# ECUCheater.net
KiCad netlist of a schematic drawn in Altium Designer
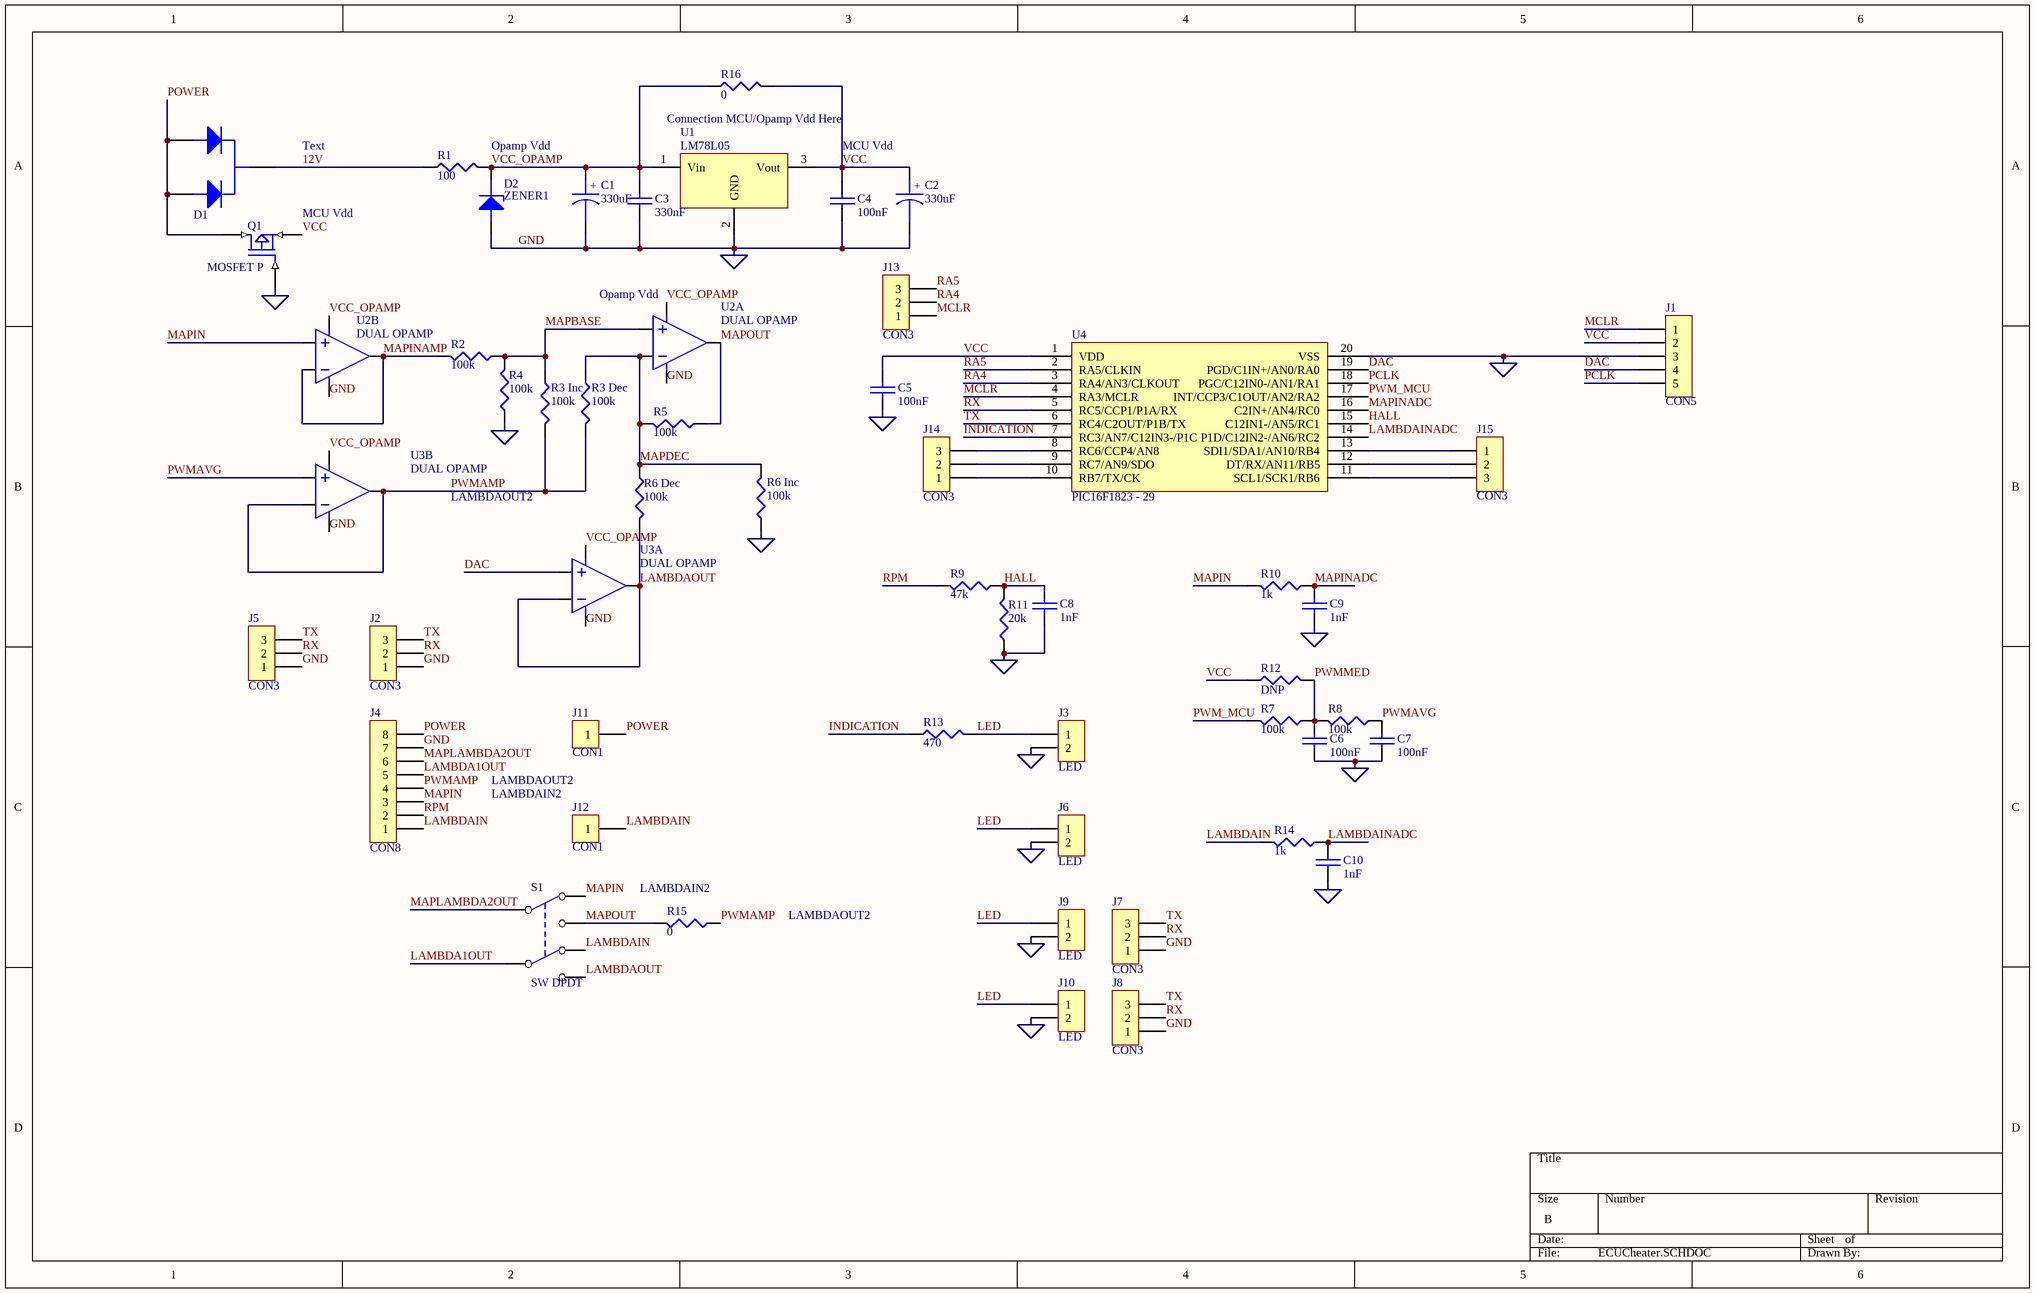
[diagram p0: ECUCheater.SCHDOC]

(export (version "E")
  (design (tool "Eeschema 10.0.6"))
  (components
    (comp (ref "C1")
      (value "330uF")
      (footprint "3528 + RA 6.3mm NOT ROUND")
      (description "Capacitor")
      (libsource (lib "*") (part "CAPACITOR POL"))
    )
    (comp (ref "C2")
      (value "330uF")
      (footprint "3528 + RA 6.3mm NOT ROUND")
      (description "Capacitor")
      (libsource (lib "*") (part "CAPACITOR POL"))
    )
    (comp (ref "C3")
      (value "330nF")
      (footprint "0805")
      (description "Capacitor")
      (libsource (lib "*") (part "CAP"))
    )
    (comp (ref "C4")
      (value "100nF")
      (footprint "0805")
      (description "Capacitor")
      (libsource (lib "*") (part "CAP"))
    )
    (comp (ref "C5")
      (value "100nF")
      (footprint "0603 CAP")
      (description "Capacitor")
      (libsource (lib "*") (part "CAP"))
    )
    (comp (ref "C6")
      (value "100nF")
      (footprint "0603 CAP")
      (description "Capacitor")
      (libsource (lib "*") (part "CAP"))
    )
    (comp (ref "C7")
      (value "100nF")
      (footprint "0603 CAP")
      (description "Capacitor")
      (libsource (lib "*") (part "CAP"))
    )
    (comp (ref "C8")
      (value "1nF")
      (footprint "0603 CAP")
      (description "Capacitor")
      (libsource (lib "*") (part "CAP"))
    )
    (comp (ref "C9")
      (value "1nF")
      (footprint "0603 CAP")
      (description "Capacitor")
      (libsource (lib "*") (part "CAP"))
    )
    (comp (ref "C10")
      (value "1nF")
      (footprint "0603 CAP")
      (description "Capacitor")
      (libsource (lib "*") (part "CAP"))
    )
    (comp (ref "D1")
      (value "DUAL DIODE BAV70")
      (footprint "SOT-23")
      (libsource (lib "Devices") (part "DUAL DIODE BAV70"))
    )
    (comp (ref "D2")
      (value "ZENER1")
      (footprint "SOT-23")
      (description "Zener Diode")
      (libsource (lib "Miscellaneous Devices") (part "ZENER1"))
    )
    (comp (ref "J1")
      (value "CON5")
      (footprint "SIP5 - PGM")
      (description "Connector")
      (libsource (lib "Miscellaneous Devices") (part "CON5"))
    )
    (comp (ref "J2")
      (value "CON3")
      (footprint "SIP3")
      (description "Connector")
      (libsource (lib "Miscellaneous Devices") (part "CON3"))
    )
    (comp (ref "J3")
      (value "LED")
      (footprint "SIP2")
      (description "Connector")
      (libsource (lib "Miscellaneous Devices") (part "CON2"))
    )
    (comp (ref "J4")
      (value "CON8")
      (footprint "HD-351 8P")
      (description "Connector")
      (libsource (lib "Miscellaneous Devices") (part "CON8"))
    )
    (comp (ref "J5")
      (value "CON3")
      (footprint "SIP3")
      (description "Connector")
      (libsource (lib "Miscellaneous Devices") (part "CON3"))
    )
    (comp (ref "J6")
      (value "LED")
      (footprint "SIP2")
      (description "Connector")
      (libsource (lib "Miscellaneous Devices") (part "CON2"))
    )
    (comp (ref "J7")
      (value "CON3")
      (footprint "SIP3")
      (description "Connector")
      (libsource (lib "Miscellaneous Devices") (part "CON3"))
    )
    (comp (ref "J8")
      (value "CON3")
      (footprint "SIP3")
      (description "Connector")
      (libsource (lib "Miscellaneous Devices") (part "CON3"))
    )
    (comp (ref "J9")
      (value "LED")
      (footprint "SIP2")
      (description "Connector")
      (libsource (lib "Miscellaneous Devices") (part "CON2"))
    )
    (comp (ref "J10")
      (value "LED")
      (footprint "SIP2")
      (description "Connector")
      (libsource (lib "Miscellaneous Devices") (part "CON2"))
    )
    (comp (ref "J11")
      (value "CON1")
      (footprint "HD-351 1P")
      (description "Connector")
      (libsource (lib "Miscellaneous Devices") (part "CON1"))
    )
    (comp (ref "J12")
      (value "CON1")
      (footprint "HD-351 1P")
      (description "Connector")
      (libsource (lib "Miscellaneous Devices") (part "CON1"))
    )
    (comp (ref "J13")
      (value "CON3")
      (footprint "SIP3")
      (description "Connector")
      (libsource (lib "Miscellaneous Devices") (part "CON3"))
    )
    (comp (ref "J14")
      (value "CON3")
      (footprint "SIP3")
      (description "Connector")
      (libsource (lib "Miscellaneous Devices") (part "CON3"))
    )
    (comp (ref "J15")
      (value "CON3")
      (footprint "SIP3")
      (description "Connector")
      (libsource (lib "") (part "CON3_1"))
    )
    (comp (ref "Q1")
      (value "MOSFET P")
      (footprint "SOT-23")
      (libsource (lib "Miscellaneous Devices") (part "MOSFET P"))
    )
    (comp (ref "R1") (value "100") (footprint "0805") (libsource (lib "Miscellaneous Devices") (part "RES1")))
    (comp (ref "R2")
      (value "100k")
      (footprint "0603 RES")
      (libsource (lib "Miscellaneous Devices") (part "RES1"))
    )
    (comp (ref "R3 Dec")
      (value "100k")
      (footprint "0603 RES")
      (libsource (lib "Miscellaneous Devices") (part "RES1"))
    )
    (comp (ref "R3 Inc")
      (value "100k")
      (footprint "0603 RES")
      (libsource (lib "Miscellaneous Devices") (part "RES1"))
    )
    (comp (ref "R4")
      (value "100k")
      (footprint "0603 RES")
      (libsource (lib "Miscellaneous Devices") (part "RES1"))
    )
    (comp (ref "R5")
      (value "100k")
      (footprint "0603 RES")
      (libsource (lib "Miscellaneous Devices") (part "RES1"))
    )
    (comp (ref "R6 Dec")
      (value "100k")
      (footprint "0603 RES")
      (libsource (lib "Miscellaneous Devices") (part "RES1"))
    )
    (comp (ref "R6 Inc")
      (value "100k")
      (footprint "0603 RES")
      (libsource (lib "Miscellaneous Devices") (part "RES1"))
    )
    (comp (ref "R7")
      (value "100k")
      (footprint "0603 RES")
      (libsource (lib "Miscellaneous Devices") (part "RES1"))
    )
    (comp (ref "R8")
      (value "100k")
      (footprint "0603 RES")
      (libsource (lib "Miscellaneous Devices") (part "RES1"))
    )
    (comp (ref "R9")
      (value "47k")
      (footprint "0603 RES")
      (libsource (lib "Miscellaneous Devices") (part "RES1"))
    )
    (comp (ref "R10")
      (value "1k")
      (footprint "0603 RES")
      (libsource (lib "Miscellaneous Devices") (part "RES1"))
    )
    (comp (ref "R11")
      (value "20k")
      (footprint "0603 RES")
      (libsource (lib "Miscellaneous Devices") (part "RES1"))
    )
    (comp (ref "R12")
      (value "DNP")
      (footprint "0603 RES")
      (libsource (lib "Miscellaneous Devices") (part "RES1"))
    )
    (comp (ref "R13")
      (value "470")
      (footprint "0603 RES")
      (libsource (lib "Miscellaneous Devices") (part "RES1"))
    )
    (comp (ref "R14")
      (value "1k")
      (footprint "0603 RES")
      (libsource (lib "Miscellaneous Devices") (part "RES1"))
    )
    (comp (ref "R15")
      (value "0")
      (footprint "0603 RES")
      (libsource (lib "Miscellaneous Devices") (part "RES1"))
    )
    (comp (ref "R16") (value "0") (footprint "0805") (libsource (lib "Miscellaneous Devices") (part "RES1")))
    (comp (ref "S1")
      (value "SW DPDT")
      (footprint "BTN P1 ZIPPO")
      (libsource (lib "Miscellaneous Devices") (part "SW DPDT"))
    )
    (comp (ref "U1") (value "LM78L05") (footprint "SO-8 VOLTREG") (libsource (lib "*") (part "VOLTREG")))
    (comp (ref "U2") (value "DUAL OPAMP") (footprint "SO-8") (libsource (lib "Devices") (part "DUAL OPAMP")))
    (comp (ref "U3") (value "DUAL OPAMP") (footprint "SO-8") (libsource (lib "Devices") (part "DUAL OPAMP")))
    (comp (ref "U4")
      (value "PIC16F1823 - 29")
      (footprint "SOIC20W SO-14")
      (description "Microchip Microcontroller")
      (libsource (lib "MCU") (part "PIC16F1828"))
    )
  )
  (nets
    (net (code "1") (name "/12V") (class "Default")
      (node (ref "D1") (pin "2") (pinfunction "K_2") (pintype "passive"))
      (node (ref "R1") (pin "1") (pinfunction "1_1") (pintype "passive"))
    )
    (net (code "2") (name "/DAC") (class "Default")
      (node (ref "J1") (pin "4") (pinfunction "4_4") (pintype "passive"))
      (node (ref "U3") (pin "3") (pinfunction "IN+_3") (pintype "passive"))
      (node (ref "U4") (pin "19") (pinfunction "PGD/C1IN+/AN0/RA0_19") (pintype "passive"))
    )
    (net (code "3") (name "/HALL") (class "Default")
      (node (ref "C8") (pin "1") (pinfunction "1_1") (pintype "passive"))
      (node (ref "R11") (pin "2") (pinfunction "2_2") (pintype "passive"))
      (node (ref "R9") (pin "1") (pinfunction "1_1") (pintype "passive"))
      (node (ref "U4") (pin "15") (pinfunction "C12IN1-/AN5/RC1_15") (pintype "passive"))
    )
    (net (code "4") (name "/INDICATION") (class "Default")
      (node (ref "R13") (pin "1") (pinfunction "1_1") (pintype "passive"))
      (node (ref "U4") (pin "7") (pinfunction "RC3/AN7/C12IN3-/P1C_7") (pintype "passive"))
    )
    (net (code "5") (name "/LAMBDA1OUT") (class "Default")
      (node (ref "J4") (pin "5") (pinfunction "5_5") (pintype "passive"))
      (node (ref "S1") (pin "6") (pinfunction "COMMON2_6") (pintype "passive"))
    )
    (net (code "6") (name "/LAMBDAIN") (class "Default")
      (node (ref "J12") (pin "1") (pinfunction "1_1") (pintype "passive"))
      (node (ref "J4") (pin "1") (pinfunction "1_1") (pintype "passive"))
      (node (ref "R14") (pin "2") (pinfunction "2_2") (pintype "passive"))
      (node (ref "S1") (pin "4") (pinfunction "NC2_4") (pintype "passive"))
    )
    (net (code "7") (name "/LAMBDAINADC") (class "Default")
      (node (ref "C10") (pin "1") (pinfunction "1_1") (pintype "passive"))
      (node (ref "R14") (pin "1") (pinfunction "1_1") (pintype "passive"))
      (node (ref "U4") (pin "14") (pinfunction "P1D/C12IN2-/AN6/RC2_14") (pintype "passive"))
    )
    (net (code "8") (name "/LAMBDAOUT") (class "Default")
      (node (ref "R6 Dec") (pin "2") (pinfunction "2_2") (pintype "passive"))
      (node (ref "S1") (pin "5") (pinfunction "NO2_5") (pintype "passive"))
      (node (ref "U3") (pin "1") (pinfunction "OUT_1") (pintype "passive"))
      (node (ref "U3") (pin "2") (pinfunction "IN-_2") (pintype "passive"))
    )
    (net (code "9") (name "/LED") (class "Default")
      (node (ref "J10") (pin "1") (pinfunction "1_1") (pintype "passive"))
      (node (ref "J3") (pin "1") (pinfunction "1_1") (pintype "passive"))
      (node (ref "J6") (pin "1") (pinfunction "1_1") (pintype "passive"))
      (node (ref "J9") (pin "1") (pinfunction "1_1") (pintype "passive"))
      (node (ref "R13") (pin "2") (pinfunction "2_2") (pintype "passive"))
    )
    (net (code "10") (name "/MAPBASE") (class "Default")
      (node (ref "R2") (pin "1") (pinfunction "1_1") (pintype "passive"))
      (node (ref "R3 Inc") (pin "1") (pinfunction "1_1") (pintype "passive"))
      (node (ref "R4") (pin "2") (pinfunction "2_2") (pintype "passive"))
      (node (ref "U2") (pin "3") (pinfunction "IN+_3") (pintype "passive"))
    )
    (net (code "11") (name "/MAPDEC") (class "Default")
      (node (ref "R3 Dec") (pin "1") (pinfunction "1_1") (pintype "passive"))
      (node (ref "R5") (pin "2") (pinfunction "2_2") (pintype "passive"))
      (node (ref "R6 Dec") (pin "1") (pinfunction "1_1") (pintype "passive"))
      (node (ref "R6 Inc") (pin "2") (pinfunction "2_2") (pintype "passive"))
      (node (ref "U2") (pin "2") (pinfunction "IN-_2") (pintype "passive"))
    )
    (net (code "12") (name "/MAPIN") (class "Default")
      (node (ref "J4") (pin "3") (pinfunction "3_3") (pintype "passive"))
      (node (ref "R10") (pin "2") (pinfunction "2_2") (pintype "passive"))
      (node (ref "S1") (pin "1") (pinfunction "NC1_1") (pintype "passive"))
      (node (ref "U2") (pin "5") (pinfunction "IN+_5") (pintype "passive"))
    )
    (net (code "13") (name "/MAPINADC") (class "Default")
      (node (ref "C9") (pin "1") (pinfunction "1_1") (pintype "passive"))
      (node (ref "R10") (pin "1") (pinfunction "1_1") (pintype "passive"))
      (node (ref "U4") (pin "16") (pinfunction "C2IN+/AN4/RC0_16") (pintype "passive"))
    )
    (net (code "14") (name "/MAPINAMP") (class "Default")
      (node (ref "R2") (pin "2") (pinfunction "2_2") (pintype "passive"))
      (node (ref "U2") (pin "6") (pinfunction "IN-_6") (pintype "passive"))
      (node (ref "U2") (pin "7") (pinfunction "OUT_7") (pintype "passive"))
    )
    (net (code "15") (name "/MAPLAMBDA2OUT") (class "Default")
      (node (ref "J4") (pin "6") (pinfunction "6_6") (pintype "passive"))
      (node (ref "S1") (pin "3") (pinfunction "COMMON1_3") (pintype "passive"))
    )
    (net (code "16") (name "/MAPOUT") (class "Default")
      (node (ref "R15") (pin "2") (pinfunction "2_2") (pintype "passive"))
      (node (ref "R5") (pin "1") (pinfunction "1_1") (pintype "passive"))
      (node (ref "S1") (pin "2") (pinfunction "NO1_2") (pintype "passive"))
      (node (ref "U2") (pin "1") (pinfunction "OUT_1") (pintype "passive"))
    )
    (net (code "17") (name "/MCLR") (class "Default")
      (node (ref "J1") (pin "1") (pinfunction "1_1") (pintype "passive"))
      (node (ref "J13") (pin "1") (pinfunction "1_1") (pintype "passive"))
      (node (ref "U4") (pin "4") (pinfunction "RA3/MCLR_4") (pintype "passive"))
    )
    (net (code "18") (name "/PCLK") (class "Default")
      (node (ref "J1") (pin "5") (pinfunction "5_5") (pintype "passive"))
      (node (ref "U4") (pin "18") (pinfunction "PGC/C12IN0-/AN1/RA1_18") (pintype "passive"))
    )
    (net (code "19") (name "/POWER") (class "Default")
      (node (ref "D1") (pin "1") (pinfunction "A1_1") (pintype "passive"))
      (node (ref "D1") (pin "3") (pinfunction "A2_3") (pintype "passive"))
      (node (ref "J11") (pin "1") (pinfunction "1_1") (pintype "passive"))
      (node (ref "J4") (pin "8") (pinfunction "8_8") (pintype "passive"))
      (node (ref "Q1") (pin "2") (pinfunction "D_2") (pintype "input"))
    )
    (net (code "20") (name "/PWMAMP") (class "Default")
      (node (ref "J4") (pin "4") (pinfunction "4_4") (pintype "passive"))
      (node (ref "R15") (pin "1") (pinfunction "1_1") (pintype "passive"))
      (node (ref "R3 Dec") (pin "2") (pinfunction "2_2") (pintype "passive"))
      (node (ref "R3 Inc") (pin "2") (pinfunction "2_2") (pintype "passive"))
      (node (ref "U3") (pin "6") (pinfunction "IN-_6") (pintype "passive"))
      (node (ref "U3") (pin "7") (pinfunction "OUT_7") (pintype "passive"))
    )
    (net (code "21") (name "/PWMAVG") (class "Default")
      (node (ref "C7") (pin "1") (pinfunction "1_1") (pintype "passive"))
      (node (ref "R8") (pin "1") (pinfunction "1_1") (pintype "passive"))
      (node (ref "U3") (pin "5") (pinfunction "IN+_5") (pintype "passive"))
    )
    (net (code "22") (name "/PWMMED") (class "Default")
      (node (ref "C6") (pin "1") (pinfunction "1_1") (pintype "passive"))
      (node (ref "R12") (pin "2") (pinfunction "2_2") (pintype "passive"))
      (node (ref "R7") (pin "1") (pinfunction "1_1") (pintype "passive"))
      (node (ref "R8") (pin "2") (pinfunction "2_2") (pintype "passive"))
    )
    (net (code "23") (name "/PWM_MCU") (class "Default")
      (node (ref "R7") (pin "2") (pinfunction "2_2") (pintype "passive"))
      (node (ref "U4") (pin "17") (pinfunction "INT/CCP3/C1OUT/AN2/RA2_17") (pintype "passive"))
    )
    (net (code "24") (name "/RA4") (class "Default")
      (node (ref "J13") (pin "2") (pinfunction "2_2") (pintype "passive"))
      (node (ref "U4") (pin "3") (pinfunction "RA4/AN3/CLKOUT_3") (pintype "passive"))
    )
    (net (code "25") (name "/RA5") (class "Default")
      (node (ref "J13") (pin "3") (pinfunction "3_3") (pintype "passive"))
      (node (ref "U4") (pin "2") (pinfunction "RA5/CLKIN_2") (pintype "passive"))
    )
    (net (code "26") (name "/RPM") (class "Default")
      (node (ref "J4") (pin "2") (pinfunction "2_2") (pintype "passive"))
      (node (ref "R9") (pin "2") (pinfunction "2_2") (pintype "passive"))
    )
    (net (code "27") (name "/RX") (class "Default")
      (node (ref "J2") (pin "2") (pinfunction "2_2") (pintype "passive"))
      (node (ref "J5") (pin "2") (pinfunction "2_2") (pintype "passive"))
      (node (ref "J7") (pin "2") (pinfunction "2_2") (pintype "passive"))
      (node (ref "J8") (pin "2") (pinfunction "2_2") (pintype "passive"))
      (node (ref "U4") (pin "5") (pinfunction "RC5/CCP1/P1A/RX_5") (pintype "passive"))
    )
    (net (code "28") (name "/TX") (class "Default")
      (node (ref "J2") (pin "3") (pinfunction "3_3") (pintype "passive"))
      (node (ref "J5") (pin "3") (pinfunction "3_3") (pintype "passive"))
      (node (ref "J7") (pin "3") (pinfunction "3_3") (pintype "passive"))
      (node (ref "J8") (pin "3") (pinfunction "3_3") (pintype "passive"))
      (node (ref "U4") (pin "6") (pinfunction "RC4/C2OUT/P1B/TX_6") (pintype "passive"))
    )
    (net (code "29") (name "/VCC") (class "Default")
      (node (ref "C2") (pin "1") (pinfunction "1_1") (pintype "passive"))
      (node (ref "C4") (pin "1") (pinfunction "1_1") (pintype "passive"))
      (node (ref "C5") (pin "1") (pinfunction "1_1") (pintype "passive"))
      (node (ref "J1") (pin "2") (pinfunction "2_2") (pintype "passive"))
      (node (ref "Q1") (pin "3") (pinfunction "S_3") (pintype "input"))
      (node (ref "R12") (pin "1") (pinfunction "1_1") (pintype "passive"))
      (node (ref "R16") (pin "2") (pinfunction "2_2") (pintype "passive"))
      (node (ref "U1") (pin "3") (pinfunction "Vout_3") (pintype "passive"))
      (node (ref "U4") (pin "1") (pinfunction "VDD_1") (pintype "passive"))
    )
    (net (code "30") (name "/VCC_OPAMP") (class "Default")
      (node (ref "C1") (pin "1") (pinfunction "1_1") (pintype "passive"))
      (node (ref "C3") (pin "1") (pinfunction "1_1") (pintype "passive"))
      (node (ref "D2") (pin "2") (pinfunction "K_2") (pintype "passive"))
      (node (ref "R1") (pin "2") (pinfunction "2_2") (pintype "passive"))
      (node (ref "R16") (pin "1") (pinfunction "1_1") (pintype "passive"))
      (node (ref "U1") (pin "1") (pinfunction "Vin_1") (pintype "passive"))
      (node (ref "U2") (pin "8") (pinfunction "V+_8") (pintype "passive"))
      (node (ref "U3") (pin "8") (pinfunction "V+_8") (pintype "passive"))
    )
    (net (code "31") (name "Net-(U4-DT{slash}RX{slash}AN11{slash}RB5)") (class "Default")
      (node (ref "J15") (pin "2") (pinfunction "2_2") (pintype "passive"))
      (node (ref "U4") (pin "12") (pinfunction "DT/RX/AN11/RB5_12") (pintype "passive"))
    )
    (net (code "32") (name "Net-(U4-RB7{slash}TX{slash}CK)") (class "Default")
      (node (ref "J14") (pin "1") (pinfunction "1_1") (pintype "passive"))
      (node (ref "U4") (pin "10") (pinfunction "RB7/TX/CK_10") (pintype "passive"))
    )
    (net (code "33") (name "Net-(U4-RC6{slash}CCP4{slash}AN8)") (class "Default")
      (node (ref "J14") (pin "3") (pinfunction "3_3") (pintype "passive"))
      (node (ref "U4") (pin "8") (pinfunction "RC6/CCP4/AN8_8") (pintype "passive"))
    )
    (net (code "34") (name "Net-(U4-RC7{slash}AN9{slash}SDO)") (class "Default")
      (node (ref "J14") (pin "2") (pinfunction "2_2") (pintype "passive"))
      (node (ref "U4") (pin "9") (pinfunction "RC7/AN9/SDO_9") (pintype "passive"))
    )
    (net (code "35") (name "Net-(U4-SCL1{slash}SCK1{slash}RB6)") (class "Default")
      (node (ref "J15") (pin "3") (pinfunction "3_3") (pintype "passive"))
      (node (ref "U4") (pin "11") (pinfunction "SCL1/SCK1/RB6_11") (pintype "passive"))
    )
    (net (code "36") (name "Net-(U4-SDI1{slash}SDA1{slash}AN10{slash}RB4)") (class "Default")
      (node (ref "J15") (pin "1") (pinfunction "1_1") (pintype "passive"))
      (node (ref "U4") (pin "13") (pinfunction "SDI1/SDA1/AN10/RB4_13") (pintype "passive"))
    )
    (net (code "37") (name "SGND") (class "Default")
      (node (ref "C1") (pin "2") (pinfunction "2_2") (pintype "passive"))
      (node (ref "C10") (pin "2") (pinfunction "2_2") (pintype "passive"))
      (node (ref "C2") (pin "2") (pinfunction "2_2") (pintype "passive"))
      (node (ref "C3") (pin "2") (pinfunction "2_2") (pintype "passive"))
      (node (ref "C4") (pin "2") (pinfunction "2_2") (pintype "passive"))
      (node (ref "C5") (pin "2") (pinfunction "2_2") (pintype "passive"))
      (node (ref "C6") (pin "2") (pinfunction "2_2") (pintype "passive"))
      (node (ref "C7") (pin "2") (pinfunction "2_2") (pintype "passive"))
      (node (ref "C8") (pin "2") (pinfunction "2_2") (pintype "passive"))
      (node (ref "C9") (pin "2") (pinfunction "2_2") (pintype "passive"))
      (node (ref "D2") (pin "1") (pinfunction "A_1") (pintype "passive"))
      (node (ref "J1") (pin "3") (pinfunction "3_3") (pintype "passive"))
      (node (ref "J10") (pin "2") (pinfunction "2_2") (pintype "passive"))
      (node (ref "J2") (pin "1") (pinfunction "1_1") (pintype "passive"))
      (node (ref "J3") (pin "2") (pinfunction "2_2") (pintype "passive"))
      (node (ref "J4") (pin "7") (pinfunction "7_7") (pintype "passive"))
      (node (ref "J5") (pin "1") (pinfunction "1_1") (pintype "passive"))
      (node (ref "J6") (pin "2") (pinfunction "2_2") (pintype "passive"))
      (node (ref "J7") (pin "1") (pinfunction "1_1") (pintype "passive"))
      (node (ref "J8") (pin "1") (pinfunction "1_1") (pintype "passive"))
      (node (ref "J9") (pin "2") (pinfunction "2_2") (pintype "passive"))
      (node (ref "Q1") (pin "1") (pinfunction "G_1") (pintype "input"))
      (node (ref "R11") (pin "1") (pinfunction "1_1") (pintype "passive"))
      (node (ref "R4") (pin "1") (pinfunction "1_1") (pintype "passive"))
      (node (ref "R6 Inc") (pin "1") (pinfunction "1_1") (pintype "passive"))
      (node (ref "U1") (pin "2") (pinfunction "GND_2") (pintype "passive"))
      (node (ref "U2") (pin "4") (pinfunction "V-_4") (pintype "passive"))
      (node (ref "U3") (pin "4") (pinfunction "V-_4") (pintype "passive"))
      (node (ref "U4") (pin "20") (pinfunction "VSS_20") (pintype "passive"))
    )
  )
)
